# polivoks_ambika.net
KiCad netlist of a schematic drawn in EAGLE
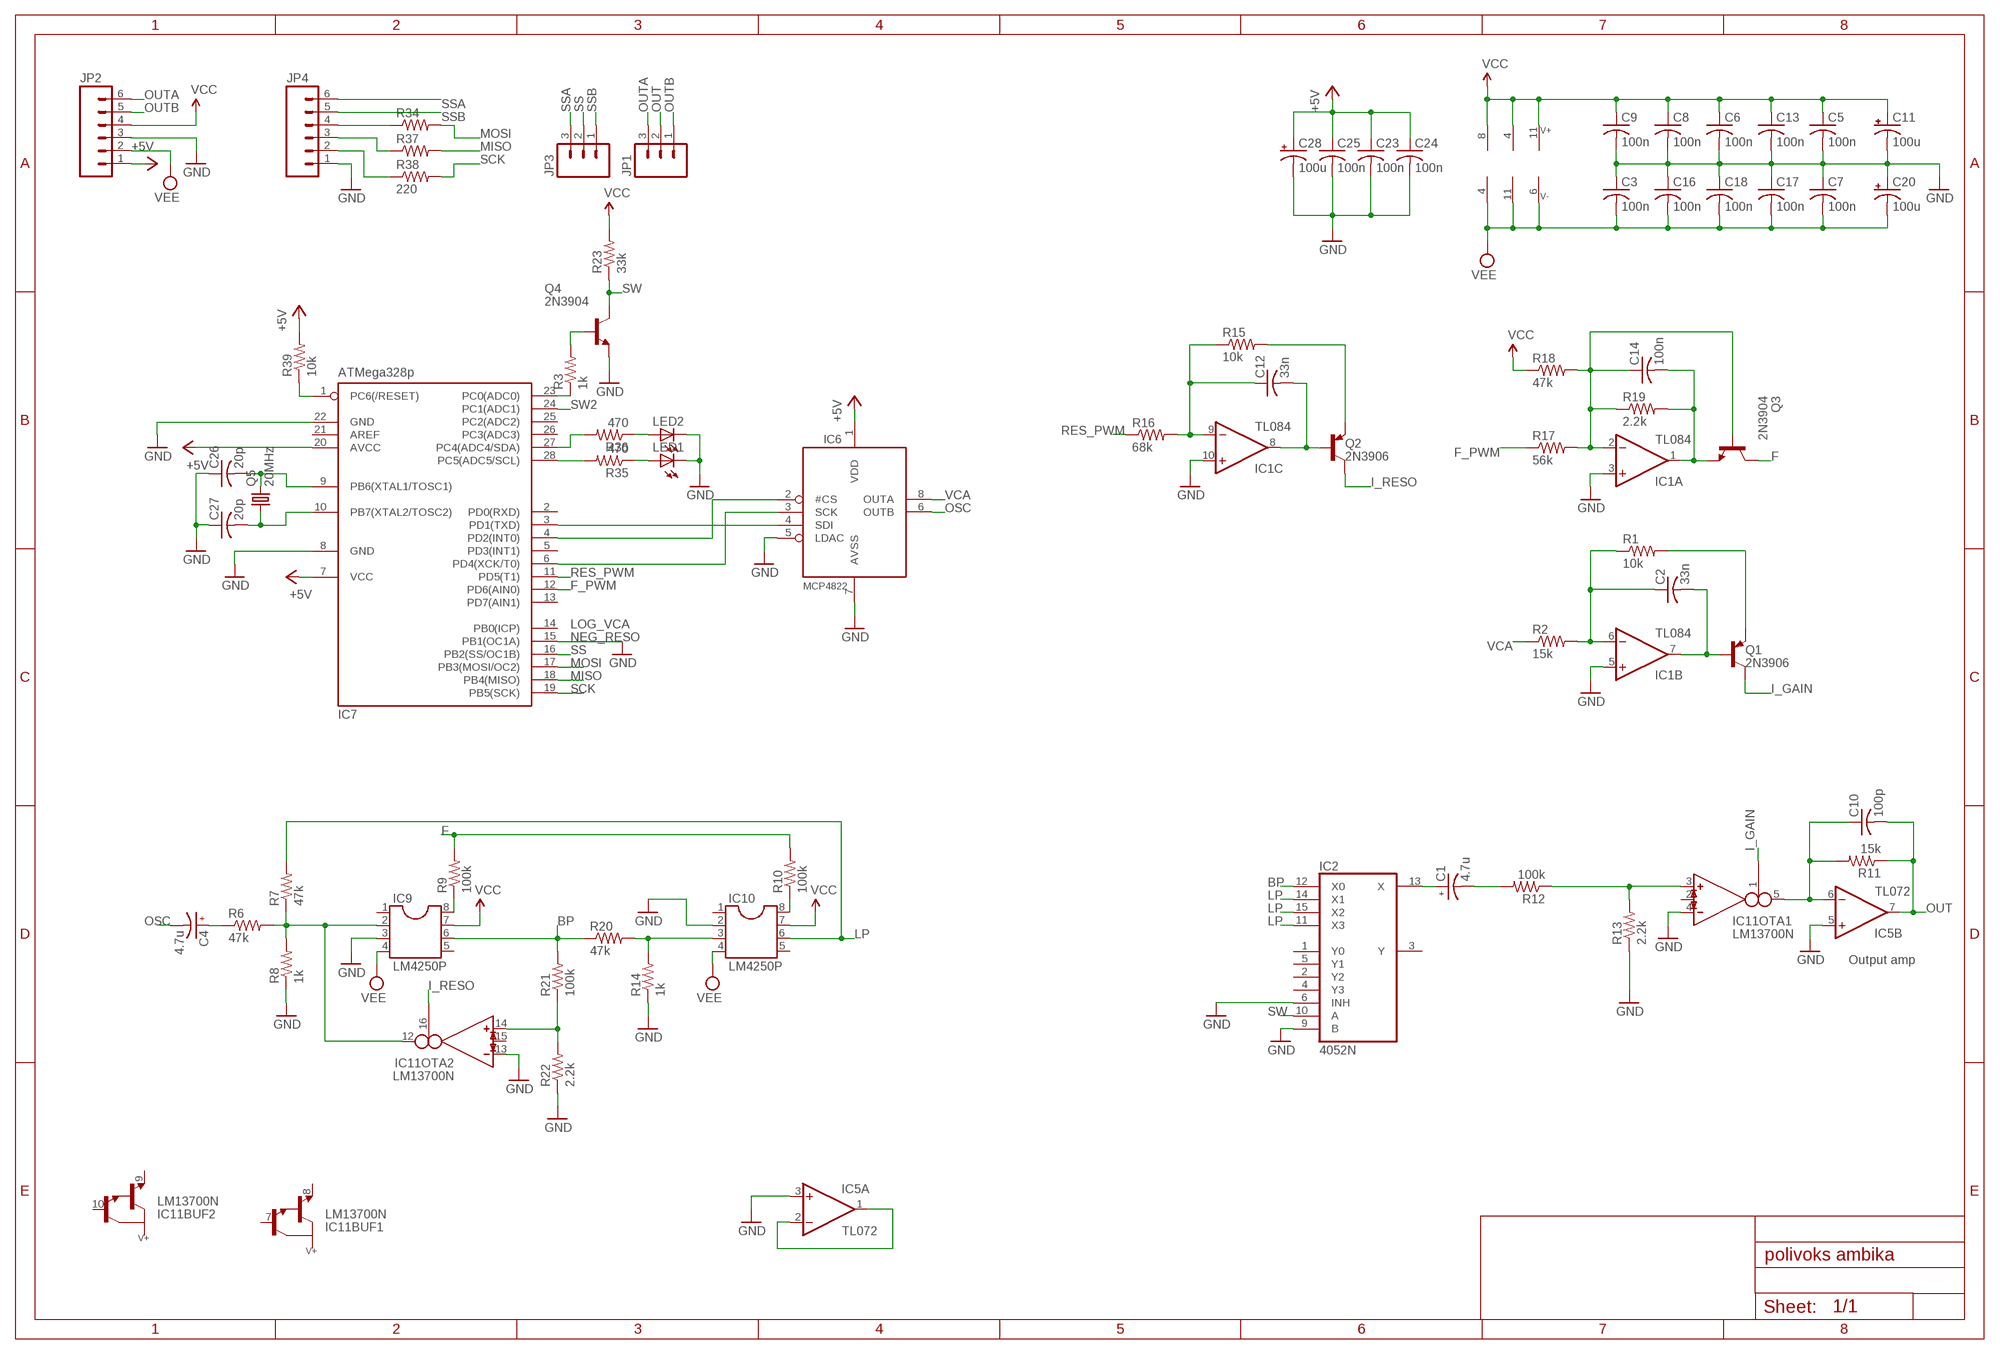
[diagram p0: schematic, sheet 1]

(export (version "E")
  (design (tool "Eeschema 10.0.6"))
  (components
    (comp (ref "C1")
      (value "4.7u")
      (footprint "eagle-import:E11-6.3")
      (libsource (lib "eagle-import") (part "CPOL-USE11-6.3"))
    )
    (comp (ref "C2")
      (value "33n")
      (footprint "eagle-import:C050-025X075")
      (libsource (lib "eagle-import") (part "C-US050-025X075"))
    )
    (comp (ref "C3")
      (value "100n")
      (footprint "eagle-import:C025-025X050")
      (libsource (lib "eagle-import") (part "C-US025-025X050"))
    )
    (comp (ref "C4")
      (value "4.7u")
      (footprint "eagle-import:E11-6.3")
      (libsource (lib "eagle-import") (part "CPOL-USE11-6.3"))
    )
    (comp (ref "C5")
      (value "100n")
      (footprint "eagle-import:C025-025X050")
      (libsource (lib "eagle-import") (part "C-US025-025X050"))
    )
    (comp (ref "C6")
      (value "100n")
      (footprint "eagle-import:C025-025X050")
      (libsource (lib "eagle-import") (part "C-US025-025X050"))
    )
    (comp (ref "C7")
      (value "100n")
      (footprint "eagle-import:C025-025X050")
      (libsource (lib "eagle-import") (part "C-US025-025X050"))
    )
    (comp (ref "C8")
      (value "100n")
      (footprint "eagle-import:C025-025X050")
      (libsource (lib "eagle-import") (part "C-US025-025X050"))
    )
    (comp (ref "C9")
      (value "100n")
      (footprint "eagle-import:C025-025X050")
      (libsource (lib "eagle-import") (part "C-US025-025X050"))
    )
    (comp (ref "C10")
      (value "100p")
      (footprint "eagle-import:C025-025X050")
      (libsource (lib "eagle-import") (part "C-US025-025X050"))
    )
    (comp (ref "C11")
      (value "100u")
      (footprint "eagle-import:E2,5-6")
      (libsource (lib "eagle-import") (part "CPOL-USE2.5-6"))
    )
    (comp (ref "C12")
      (value "33n")
      (footprint "eagle-import:C050-025X075")
      (libsource (lib "eagle-import") (part "C-US050-025X075"))
    )
    (comp (ref "C13")
      (value "100n")
      (footprint "eagle-import:C025-025X050")
      (libsource (lib "eagle-import") (part "C-US025-025X050"))
    )
    (comp (ref "C14")
      (value "100n")
      (footprint "eagle-import:C025-025X050")
      (libsource (lib "eagle-import") (part "C-US025-025X050"))
    )
    (comp (ref "C16")
      (value "100n")
      (footprint "eagle-import:C025-025X050")
      (libsource (lib "eagle-import") (part "C-US025-025X050"))
    )
    (comp (ref "C17")
      (value "100n")
      (footprint "eagle-import:C025-025X050")
      (libsource (lib "eagle-import") (part "C-US025-025X050"))
    )
    (comp (ref "C18")
      (value "100n")
      (footprint "eagle-import:C025-025X050")
      (libsource (lib "eagle-import") (part "C-US025-025X050"))
    )
    (comp (ref "C20")
      (value "100u")
      (footprint "eagle-import:E2,5-6")
      (libsource (lib "eagle-import") (part "CPOL-USE2.5-6"))
    )
    (comp (ref "C23")
      (value "100n")
      (footprint "eagle-import:C025-025X050")
      (libsource (lib "eagle-import") (part "C-US025-025X050"))
    )
    (comp (ref "C24")
      (value "100n")
      (footprint "eagle-import:C025-025X050")
      (libsource (lib "eagle-import") (part "C-US025-025X050"))
    )
    (comp (ref "C25")
      (value "100n")
      (footprint "eagle-import:C025-025X050")
      (libsource (lib "eagle-import") (part "C-US025-025X050"))
    )
    (comp (ref "C26")
      (value "20p")
      (footprint "eagle-import:C025-024X044")
      (libsource (lib "eagle-import") (part "C-US025-024X044"))
    )
    (comp (ref "C27")
      (value "20p")
      (footprint "eagle-import:C025-024X044")
      (libsource (lib "eagle-import") (part "C-US025-024X044"))
    )
    (comp (ref "C28")
      (value "100u")
      (footprint "eagle-import:E2,5-6")
      (libsource (lib "eagle-import") (part "CPOL-USE2.5-6"))
    )
    (comp (ref "IC1")
      (value "TL084")
      (footprint "eagle-import:DIL14")
      (libsource (lib "eagle-import") (part "TL084P"))
    )
    (comp (ref "IC2")
      (value "4052N")
      (footprint "eagle-import:DIL16")
      (libsource (lib "eagle-import") (part "4052N"))
    )
    (comp (ref "IC5")
      (value "TL072")
      (footprint "eagle-import:DIL08")
      (libsource (lib "eagle-import") (part "TL082P"))
    )
    (comp (ref "IC6")
      (value "MCP4822")
      (footprint "eagle-import:DIL08")
      (libsource (lib "eagle-import") (part "MCP4822"))
    )
    (comp (ref "IC7")
      (value "ATMega328p")
      (footprint "eagle-import:DIL28-3")
      (libsource (lib "eagle-import") (part "MEGA8-P"))
    )
    (comp (ref "IC9")
      (value "LM4250P")
      (footprint "eagle-import:DIL08")
      (libsource (lib "eagle-import") (part "DIL8"))
    )
    (comp (ref "IC10")
      (value "LM4250P")
      (footprint "eagle-import:DIL08")
      (libsource (lib "eagle-import") (part "DIL8"))
    )
    (comp (ref "IC11")
      (value "LM13700N")
      (footprint "eagle-import:DIL16")
      (libsource (lib "eagle-import") (part "LM13700N"))
    )
    (comp (ref "JP1")
      (value "M03PTH")
      (footprint "eagle-import:1X03")
      (libsource (lib "eagle-import") (part "M03PTH"))
    )
    (comp (ref "JP2")
      (value "M06SIP")
      (footprint "eagle-import:1X06")
      (libsource (lib "eagle-import") (part "M06SIP"))
    )
    (comp (ref "JP3")
      (value "M03PTH")
      (footprint "eagle-import:1X03")
      (libsource (lib "eagle-import") (part "M03PTH"))
    )
    (comp (ref "JP4")
      (value "M06SIP")
      (footprint "eagle-import:1X06")
      (libsource (lib "eagle-import") (part "M06SIP"))
    )
    (comp (ref "LED1")
      (value "LED3MM")
      (footprint "eagle-import:LED3MM")
      (libsource (lib "eagle-import") (part "LED3MM"))
    )
    (comp (ref "LED2")
      (value "LED3MM")
      (footprint "eagle-import:LED3MM")
      (libsource (lib "eagle-import") (part "LED3MM"))
    )
    (comp (ref "Q1")
      (value "2N3906")
      (footprint "eagle-import:TO92-")
      (libsource (lib "eagle-import") (part "2N3906-"))
    )
    (comp (ref "Q2")
      (value "2N3906")
      (footprint "eagle-import:TO92-")
      (libsource (lib "eagle-import") (part "2N3906-"))
    )
    (comp (ref "Q3")
      (value "2N3904")
      (footprint "eagle-import:TO92")
      (libsource (lib "eagle-import") (part "2N3904"))
    )
    (comp (ref "Q4")
      (value "2N3904")
      (footprint "eagle-import:TO92")
      (libsource (lib "eagle-import") (part "2N3904"))
    )
    (comp (ref "Q5")
      (value "20MHz")
      (footprint "eagle-import:HC49U-V")
      (libsource (lib "eagle-import") (part "CRYSTALHC49U-V"))
    )
    (comp (ref "R1")
      (value "10k")
      (footprint "eagle-import:0204_7")
      (libsource (lib "eagle-import") (part "R-US_0204/7"))
    )
    (comp (ref "R2")
      (value "15k")
      (footprint "eagle-import:0204_7")
      (libsource (lib "eagle-import") (part "R-US_0204/7"))
    )
    (comp (ref "R3")
      (value "1k")
      (footprint "eagle-import:0204_7")
      (libsource (lib "eagle-import") (part "R-US_0204/7"))
    )
    (comp (ref "R6")
      (value "47k")
      (footprint "eagle-import:0204_7")
      (libsource (lib "eagle-import") (part "R-US_0204/7"))
    )
    (comp (ref "R7")
      (value "47k")
      (footprint "eagle-import:0204_7")
      (libsource (lib "eagle-import") (part "R-US_0204/7"))
    )
    (comp (ref "R8")
      (value "1k")
      (footprint "eagle-import:0204_7")
      (libsource (lib "eagle-import") (part "R-US_0204/7"))
    )
    (comp (ref "R9")
      (value "100k")
      (footprint "eagle-import:0204_7")
      (libsource (lib "eagle-import") (part "R-US_0204/7"))
    )
    (comp (ref "R10")
      (value "100k")
      (footprint "eagle-import:0204_7")
      (libsource (lib "eagle-import") (part "R-US_0204/7"))
    )
    (comp (ref "R11")
      (value "15k")
      (footprint "eagle-import:0204_7")
      (libsource (lib "eagle-import") (part "R-US_0204/7"))
    )
    (comp (ref "R12")
      (value "100k")
      (footprint "eagle-import:0204_7")
      (libsource (lib "eagle-import") (part "R-US_0204/7"))
    )
    (comp (ref "R13")
      (value "2.2k")
      (footprint "eagle-import:0204_7")
      (libsource (lib "eagle-import") (part "R-US_0204/7"))
    )
    (comp (ref "R14")
      (value "1k")
      (footprint "eagle-import:0204_7")
      (libsource (lib "eagle-import") (part "R-US_0204/7"))
    )
    (comp (ref "R15")
      (value "10k")
      (footprint "eagle-import:0204_7")
      (libsource (lib "eagle-import") (part "R-US_0204/7"))
    )
    (comp (ref "R16")
      (value "68k")
      (footprint "eagle-import:0204_7")
      (libsource (lib "eagle-import") (part "R-US_0204/7"))
    )
    (comp (ref "R17")
      (value "56k")
      (footprint "eagle-import:0204_7")
      (libsource (lib "eagle-import") (part "R-US_0204/7"))
    )
    (comp (ref "R18")
      (value "47k")
      (footprint "eagle-import:0204_7")
      (libsource (lib "eagle-import") (part "R-US_0204/7"))
    )
    (comp (ref "R19")
      (value "2.2k")
      (footprint "eagle-import:0204_7")
      (libsource (lib "eagle-import") (part "R-US_0204/7"))
    )
    (comp (ref "R20")
      (value "47k")
      (footprint "eagle-import:0204_7")
      (libsource (lib "eagle-import") (part "R-US_0204/7"))
    )
    (comp (ref "R21")
      (value "100k")
      (footprint "eagle-import:0204_7")
      (libsource (lib "eagle-import") (part "R-US_0204/7"))
    )
    (comp (ref "R22")
      (value "2.2k")
      (footprint "eagle-import:0204_7")
      (libsource (lib "eagle-import") (part "R-US_0204/7"))
    )
    (comp (ref "R23")
      (value "33k")
      (footprint "eagle-import:0204_7")
      (libsource (lib "eagle-import") (part "R-US_0204/7"))
    )
    (comp (ref "R34")
      (value "220")
      (footprint "eagle-import:0204_7")
      (libsource (lib "eagle-import") (part "R-US_0204/7"))
    )
    (comp (ref "R35")
      (value "470")
      (footprint "eagle-import:0204_7")
      (libsource (lib "eagle-import") (part "R-US_0204/7"))
    )
    (comp (ref "R36")
      (value "470")
      (footprint "eagle-import:0204_7")
      (libsource (lib "eagle-import") (part "R-US_0204/7"))
    )
    (comp (ref "R37")
      (value "220")
      (footprint "eagle-import:0204_7")
      (libsource (lib "eagle-import") (part "R-US_0204/7"))
    )
    (comp (ref "R38")
      (value "220")
      (footprint "eagle-import:0204_7")
      (libsource (lib "eagle-import") (part "R-US_0204/7"))
    )
    (comp (ref "R39")
      (value "10k")
      (footprint "eagle-import:0204_7")
      (libsource (lib "eagle-import") (part "R-US_0204/7"))
    )
  )
  (nets
    (net (code "1") (name "+5V") (class "Default")
      (node (ref "C23") (pin "1") (pinfunction "1_1") (pintype "passive"))
      (node (ref "C24") (pin "1") (pinfunction "1_1") (pintype "passive"))
      (node (ref "C25") (pin "1") (pinfunction "1_1") (pintype "passive"))
      (node (ref "C28") (pin "+") (pinfunction "+_+") (pintype "passive"))
      (node (ref "IC6") (pin "1") (pinfunction "VDD_1") (pintype "power_in"))
      (node (ref "IC7") (pin "20") (pinfunction "AVCC_20") (pintype "power_in"))
      (node (ref "IC7") (pin "7") (pinfunction "VCC_7") (pintype "power_in"))
      (node (ref "JP2") (pin "1") (pinfunction "1_1") (pintype "passive"))
      (node (ref "R39") (pin "2") (pinfunction "2_2") (pintype "passive"))
    )
    (net (code "2") (name "/BP") (class "Default")
      (node (ref "IC2") (pin "12") (pinfunction "X0_12") (pintype "bidirectional"))
      (node (ref "IC9") (pin "6") (pinfunction "6_6") (pintype "passive"))
      (node (ref "R20") (pin "1") (pinfunction "1_1") (pintype "passive"))
      (node (ref "R21") (pin "2") (pinfunction "2_2") (pintype "passive"))
    )
    (net (code "3") (name "/F") (class "Default")
      (node (ref "Q3") (pin "1") (pinfunction "C_1") (pintype "passive"))
      (node (ref "R10") (pin "2") (pinfunction "2_2") (pintype "passive"))
      (node (ref "R9") (pin "2") (pinfunction "2_2") (pintype "passive"))
    )
    (net (code "4") (name "/F_PWM") (class "Default")
      (node (ref "IC7") (pin "12") (pinfunction "PD6(AIN0)_12") (pintype "bidirectional"))
      (node (ref "R17") (pin "1") (pinfunction "1_1") (pintype "passive"))
    )
    (net (code "5") (name "/I_GAIN") (class "Default")
      (node (ref "IC11") (pin "1") (pinfunction "I_BIAS_1") (pintype "input"))
      (node (ref "Q1") (pin "1") (pinfunction "C_1") (pintype "passive"))
    )
    (net (code "6") (name "/I_RESO") (class "Default")
      (node (ref "IC11") (pin "16") (pinfunction "I_BIAS_16") (pintype "input"))
      (node (ref "Q2") (pin "1") (pinfunction "C_1") (pintype "passive"))
    )
    (net (code "7") (name "/LP") (class "Default")
      (node (ref "IC10") (pin "6") (pinfunction "6_6") (pintype "passive"))
      (node (ref "IC2") (pin "11") (pinfunction "X3_11") (pintype "bidirectional"))
      (node (ref "IC2") (pin "14") (pinfunction "X1_14") (pintype "bidirectional"))
      (node (ref "IC2") (pin "15") (pinfunction "X2_15") (pintype "bidirectional"))
      (node (ref "R7") (pin "2") (pinfunction "2_2") (pintype "passive"))
    )
    (net (code "8") (name "/MISO") (class "Default")
      (node (ref "IC7") (pin "18") (pinfunction "PB4(MISO)_18") (pintype "bidirectional"))
      (node (ref "R37") (pin "2") (pinfunction "2_2") (pintype "passive"))
    )
    (net (code "9") (name "/MOSI") (class "Default")
      (node (ref "IC7") (pin "17") (pinfunction "PB3(MOSI/OC2)_17") (pintype "bidirectional"))
      (node (ref "R34") (pin "2") (pinfunction "2_2") (pintype "passive"))
    )
    (net (code "10") (name "/OSC") (class "Default")
      (node (ref "C4") (pin "-") (pinfunction "2_-") (pintype "passive"))
      (node (ref "IC6") (pin "6") (pinfunction "OUTB_6") (pintype "output"))
    )
    (net (code "11") (name "/OUT") (class "Default")
      (node (ref "C10") (pin "2") (pinfunction "2_2") (pintype "passive"))
      (node (ref "IC5") (pin "7") (pinfunction "OUT_7") (pintype "output"))
      (node (ref "JP1") (pin "2") (pinfunction "2_2") (pintype "passive"))
      (node (ref "R11") (pin "1") (pinfunction "1_1") (pintype "passive"))
    )
    (net (code "12") (name "/OUTA") (class "Default")
      (node (ref "JP1") (pin "3") (pinfunction "3_3") (pintype "passive"))
      (node (ref "JP2") (pin "6") (pinfunction "6_6") (pintype "passive"))
    )
    (net (code "13") (name "/OUTB") (class "Default")
      (node (ref "JP1") (pin "1") (pinfunction "1_1") (pintype "passive"))
      (node (ref "JP2") (pin "5") (pinfunction "5_5") (pintype "passive"))
    )
    (net (code "14") (name "/RES_PWM") (class "Default")
      (node (ref "IC7") (pin "11") (pinfunction "PD5(T1)_11") (pintype "bidirectional"))
      (node (ref "R16") (pin "1") (pinfunction "1_1") (pintype "passive"))
    )
    (net (code "15") (name "/SCK") (class "Default")
      (node (ref "IC7") (pin "19") (pinfunction "PB5(SCK)_19") (pintype "bidirectional"))
      (node (ref "R38") (pin "2") (pinfunction "2_2") (pintype "passive"))
    )
    (net (code "16") (name "/SS") (class "Default")
      (node (ref "IC7") (pin "16") (pinfunction "PB2(SS/OC1B)_16") (pintype "bidirectional"))
      (node (ref "JP3") (pin "2") (pinfunction "2_2") (pintype "passive"))
    )
    (net (code "17") (name "/SSA") (class "Default")
      (node (ref "JP3") (pin "3") (pinfunction "3_3") (pintype "passive"))
      (node (ref "JP4") (pin "6") (pinfunction "6_6") (pintype "passive"))
    )
    (net (code "18") (name "/SSB") (class "Default")
      (node (ref "JP3") (pin "1") (pinfunction "1_1") (pintype "passive"))
      (node (ref "JP4") (pin "5") (pinfunction "5_5") (pintype "passive"))
    )
    (net (code "19") (name "/SW") (class "Default")
      (node (ref "IC2") (pin "10") (pinfunction "A_10") (pintype "input"))
      (node (ref "Q4") (pin "1") (pinfunction "C_1") (pintype "passive"))
      (node (ref "R23") (pin "1") (pinfunction "1_1") (pintype "passive"))
    )
    (net (code "20") (name "/SW2") (class "Default")
      (node (ref "IC7") (pin "24") (pinfunction "PC1(ADC1)_24") (pintype "bidirectional"))
    )
    (net (code "21") (name "/VCA") (class "Default")
      (node (ref "IC6") (pin "8") (pinfunction "OUTA_8") (pintype "output"))
      (node (ref "R2") (pin "1") (pinfunction "1_1") (pintype "passive"))
    )
    (net (code "22") (name "GND") (class "Default")
      (node (ref "C11") (pin "-") (pinfunction "-_-") (pintype "passive"))
      (node (ref "C13") (pin "2") (pinfunction "2_2") (pintype "passive"))
      (node (ref "C16") (pin "1") (pinfunction "1_1") (pintype "passive"))
      (node (ref "C17") (pin "1") (pinfunction "1_1") (pintype "passive"))
      (node (ref "C18") (pin "1") (pinfunction "1_1") (pintype "passive"))
      (node (ref "C20") (pin "+") (pinfunction "+_+") (pintype "passive"))
      (node (ref "C23") (pin "2") (pinfunction "2_2") (pintype "passive"))
      (node (ref "C24") (pin "2") (pinfunction "2_2") (pintype "passive"))
      (node (ref "C25") (pin "2") (pinfunction "2_2") (pintype "passive"))
      (node (ref "C26") (pin "1") (pinfunction "1_1") (pintype "passive"))
      (node (ref "C27") (pin "1") (pinfunction "1_1") (pintype "passive"))
      (node (ref "C28") (pin "-") (pinfunction "-_-") (pintype "passive"))
      (node (ref "C3") (pin "1") (pinfunction "1_1") (pintype "passive"))
      (node (ref "C5") (pin "2") (pinfunction "2_2") (pintype "passive"))
      (node (ref "C6") (pin "2") (pinfunction "2_2") (pintype "passive"))
      (node (ref "C7") (pin "1") (pinfunction "1_1") (pintype "passive"))
      (node (ref "C8") (pin "2") (pinfunction "2_2") (pintype "passive"))
      (node (ref "C9") (pin "2") (pinfunction "2_2") (pintype "passive"))
      (node (ref "IC1") (pin "10") (pinfunction "+IN_10") (pintype "input"))
      (node (ref "IC1") (pin "3") (pinfunction "+IN_3") (pintype "input"))
      (node (ref "IC1") (pin "5") (pinfunction "+IN_5") (pintype "input"))
      (node (ref "IC10") (pin "2") (pinfunction "2_2") (pintype "passive"))
      (node (ref "IC11") (pin "13") (pinfunction "IN_N_13") (pintype "input"))
      (node (ref "IC11") (pin "4") (pinfunction "IN_N_4") (pintype "input"))
      (node (ref "IC2") (pin "6") (pinfunction "INH_6") (pintype "input"))
      (node (ref "IC2") (pin "9") (pinfunction "B_9") (pintype "input"))
      (node (ref "IC5") (pin "3") (pinfunction "+IN_3") (pintype "input"))
      (node (ref "IC5") (pin "5") (pinfunction "+IN_5") (pintype "input"))
      (node (ref "IC6") (pin "5") (pinfunction "LDAC_5") (pintype "input"))
      (node (ref "IC6") (pin "7") (pinfunction "AVSS_7") (pintype "power_in"))
      (node (ref "IC7") (pin "15") (pinfunction "PB1(OC1A)_15") (pintype "bidirectional"))
      (node (ref "IC7") (pin "22") (pinfunction "GND_22") (pintype "power_in"))
      (node (ref "IC7") (pin "8") (pinfunction "GND_8") (pintype "power_in"))
      (node (ref "IC9") (pin "3") (pinfunction "3_3") (pintype "passive"))
      (node (ref "JP2") (pin "3") (pinfunction "3_3") (pintype "passive"))
      (node (ref "JP4") (pin "1") (pinfunction "1_1") (pintype "passive"))
      (node (ref "LED1") (pin "K") (pinfunction "C_K") (pintype "passive"))
      (node (ref "LED2") (pin "K") (pinfunction "C_K") (pintype "passive"))
      (node (ref "Q4") (pin "3") (pinfunction "E_3") (pintype "passive"))
      (node (ref "R13") (pin "1") (pinfunction "1_1") (pintype "passive"))
      (node (ref "R14") (pin "1") (pinfunction "1_1") (pintype "passive"))
      (node (ref "R22") (pin "1") (pinfunction "1_1") (pintype "passive"))
      (node (ref "R8") (pin "1") (pinfunction "1_1") (pintype "passive"))
    )
    (net (code "23") (name "Net-(C1-1)") (class "Default")
      (node (ref "C1") (pin "+") (pinfunction "1_+") (pintype "passive"))
      (node (ref "IC2") (pin "13") (pinfunction "X_13") (pintype "bidirectional"))
    )
    (net (code "24") (name "Net-(C1-2)") (class "Default")
      (node (ref "C1") (pin "-") (pinfunction "2_-") (pintype "passive"))
      (node (ref "R12") (pin "2") (pinfunction "2_2") (pintype "passive"))
    )
    (net (code "25") (name "Net-(C4-1)") (class "Default")
      (node (ref "C4") (pin "+") (pinfunction "1_+") (pintype "passive"))
      (node (ref "R6") (pin "1") (pinfunction "1_1") (pintype "passive"))
    )
    (net (code "26") (name "Net-(IC1A--IN)") (class "Default")
      (node (ref "C14") (pin "1") (pinfunction "1_1") (pintype "passive"))
      (node (ref "IC1") (pin "2") (pinfunction "-IN_2") (pintype "input"))
      (node (ref "Q3") (pin "2") (pinfunction "B_2") (pintype "passive"))
      (node (ref "R17") (pin "2") (pinfunction "2_2") (pintype "passive"))
      (node (ref "R18") (pin "2") (pinfunction "2_2") (pintype "passive"))
      (node (ref "R19") (pin "1") (pinfunction "1_1") (pintype "passive"))
    )
    (net (code "27") (name "Net-(IC1A-OUT)") (class "Default")
      (node (ref "C14") (pin "2") (pinfunction "2_2") (pintype "passive"))
      (node (ref "IC1") (pin "1") (pinfunction "OUT_1") (pintype "output"))
      (node (ref "Q3") (pin "3") (pinfunction "E_3") (pintype "passive"))
      (node (ref "R19") (pin "2") (pinfunction "2_2") (pintype "passive"))
    )
    (net (code "28") (name "Net-(IC1B--IN)") (class "Default")
      (node (ref "C2") (pin "1") (pinfunction "1_1") (pintype "passive"))
      (node (ref "IC1") (pin "6") (pinfunction "-IN_6") (pintype "input"))
      (node (ref "R1") (pin "1") (pinfunction "1_1") (pintype "passive"))
      (node (ref "R2") (pin "2") (pinfunction "2_2") (pintype "passive"))
    )
    (net (code "29") (name "Net-(IC1B-OUT)") (class "Default")
      (node (ref "C2") (pin "2") (pinfunction "2_2") (pintype "passive"))
      (node (ref "IC1") (pin "7") (pinfunction "OUT_7") (pintype "output"))
      (node (ref "Q1") (pin "2") (pinfunction "B_2") (pintype "passive"))
    )
    (net (code "30") (name "Net-(IC1C--IN)") (class "Default")
      (node (ref "C12") (pin "1") (pinfunction "1_1") (pintype "passive"))
      (node (ref "IC1") (pin "9") (pinfunction "-IN_9") (pintype "input"))
      (node (ref "R15") (pin "1") (pinfunction "1_1") (pintype "passive"))
      (node (ref "R16") (pin "2") (pinfunction "2_2") (pintype "passive"))
    )
    (net (code "31") (name "Net-(IC1C-OUT)") (class "Default")
      (node (ref "C12") (pin "2") (pinfunction "2_2") (pintype "passive"))
      (node (ref "IC1") (pin "8") (pinfunction "OUT_8") (pintype "output"))
      (node (ref "Q2") (pin "2") (pinfunction "B_2") (pintype "passive"))
    )
    (net (code "32") (name "Net-(IC5A--IN)") (class "Default")
      (node (ref "IC5") (pin "1") (pinfunction "OUT_1") (pintype "output"))
      (node (ref "IC5") (pin "2") (pinfunction "-IN_2") (pintype "input"))
    )
    (net (code "33") (name "Net-(IC6-#CS)") (class "Default")
      (node (ref "IC6") (pin "2") (pinfunction "#CS_2") (pintype "input"))
      (node (ref "IC7") (pin "4") (pinfunction "PD2(INT0)_4") (pintype "bidirectional"))
    )
    (net (code "34") (name "Net-(IC6-SCK)") (class "Default")
      (node (ref "IC6") (pin "3") (pinfunction "SCK_3") (pintype "input"))
      (node (ref "IC7") (pin "6") (pinfunction "PD4(XCK/T0)_6") (pintype "bidirectional"))
    )
    (net (code "35") (name "Net-(IC6-SDI)") (class "Default")
      (node (ref "IC6") (pin "4") (pinfunction "SDI_4") (pintype "input"))
      (node (ref "IC7") (pin "3") (pinfunction "PD1(TXD)_3") (pintype "bidirectional"))
    )
    (net (code "36") (name "Net-(IC7-PB6(XTAL1{slash}TOSC1))") (class "Default")
      (node (ref "C26") (pin "2") (pinfunction "2_2") (pintype "passive"))
      (node (ref "IC7") (pin "9") (pinfunction "PB6(XTAL1/TOSC1)_9") (pintype "bidirectional"))
      (node (ref "Q5") (pin "2") (pinfunction "2_2") (pintype "passive"))
    )
    (net (code "37") (name "Net-(IC7-PB7(XTAL2{slash}TOSC2))") (class "Default")
      (node (ref "C27") (pin "2") (pinfunction "2_2") (pintype "passive"))
      (node (ref "IC7") (pin "10") (pinfunction "PB7(XTAL2/TOSC2)_10") (pintype "bidirectional"))
      (node (ref "Q5") (pin "1") (pinfunction "1_1") (pintype "passive"))
    )
    (net (code "38") (name "Net-(IC7-PC0(ADC0))") (class "Default")
      (node (ref "IC7") (pin "23") (pinfunction "PC0(ADC0)_23") (pintype "bidirectional"))
      (node (ref "R3") (pin "1") (pinfunction "1_1") (pintype "passive"))
    )
    (net (code "39") (name "Net-(IC7-PC4(ADC4{slash}SDA))") (class "Default")
      (node (ref "IC7") (pin "27") (pinfunction "PC4(ADC4/SDA)_27") (pintype "bidirectional"))
      (node (ref "R36") (pin "2") (pinfunction "2_2") (pintype "passive"))
    )
    (net (code "40") (name "Net-(IC7-PC5(ADC5{slash}SCL))") (class "Default")
      (node (ref "IC7") (pin "28") (pinfunction "PC5(ADC5/SCL)_28") (pintype "bidirectional"))
      (node (ref "R35") (pin "2") (pinfunction "2_2") (pintype "passive"))
    )
    (net (code "41") (name "Net-(IC7-PC6({slash}RESET))") (class "Default")
      (node (ref "IC7") (pin "1") (pinfunction "PC6(/RESET)_1") (pintype "bidirectional"))
      (node (ref "R39") (pin "1") (pinfunction "1_1") (pintype "passive"))
    )
    (net (code "42") (name "Net-(IC9-Pad8)") (class "Default")
      (node (ref "IC9") (pin "8") (pinfunction "8_8") (pintype "passive"))
      (node (ref "R9") (pin "1") (pinfunction "1_1") (pintype "passive"))
    )
    (net (code "43") (name "Net-(IC10-Pad3)") (class "Default")
      (node (ref "IC10") (pin "3") (pinfunction "3_3") (pintype "passive"))
      (node (ref "R14") (pin "2") (pinfunction "2_2") (pintype "passive"))
      (node (ref "R20") (pin "2") (pinfunction "2_2") (pintype "passive"))
    )
    (net (code "44") (name "Net-(IC10-Pad8)") (class "Default")
      (node (ref "IC10") (pin "8") (pinfunction "8_8") (pintype "passive"))
      (node (ref "R10") (pin "1") (pinfunction "1_1") (pintype "passive"))
    )
    (net (code "45") (name "Net-(IC11C-IN_P)") (class "Default")
      (node (ref "IC11") (pin "3") (pinfunction "IN_P_3") (pintype "input"))
      (node (ref "R12") (pin "1") (pinfunction "1_1") (pintype "passive"))
      (node (ref "R13") (pin "2") (pinfunction "2_2") (pintype "passive"))
    )
    (net (code "46") (name "Net-(IC11C-OUT)") (class "Default")
      (node (ref "C10") (pin "1") (pinfunction "1_1") (pintype "passive"))
      (node (ref "IC11") (pin "5") (pinfunction "OUT_5") (pintype "output"))
      (node (ref "IC5") (pin "6") (pinfunction "-IN_6") (pintype "input"))
      (node (ref "R11") (pin "2") (pinfunction "2_2") (pintype "passive"))
    )
    (net (code "47") (name "Net-(IC11D-IN_P)") (class "Default")
      (node (ref "IC11") (pin "14") (pinfunction "IN_P_14") (pintype "input"))
      (node (ref "R21") (pin "1") (pinfunction "1_1") (pintype "passive"))
      (node (ref "R22") (pin "2") (pinfunction "2_2") (pintype "passive"))
    )
    (net (code "48") (name "Net-(IC11D-OUT)") (class "Default")
      (node (ref "IC11") (pin "12") (pinfunction "OUT_12") (pintype "output"))
      (node (ref "IC9") (pin "2") (pinfunction "2_2") (pintype "passive"))
      (node (ref "R6") (pin "2") (pinfunction "2_2") (pintype "passive"))
      (node (ref "R7") (pin "1") (pinfunction "1_1") (pintype "passive"))
      (node (ref "R8") (pin "2") (pinfunction "2_2") (pintype "passive"))
    )
    (net (code "49") (name "Net-(JP4-Pad2)") (class "Default")
      (node (ref "JP4") (pin "2") (pinfunction "2_2") (pintype "passive"))
      (node (ref "R38") (pin "1") (pinfunction "1_1") (pintype "passive"))
    )
    (net (code "50") (name "Net-(JP4-Pad3)") (class "Default")
      (node (ref "JP4") (pin "3") (pinfunction "3_3") (pintype "passive"))
      (node (ref "R37") (pin "1") (pinfunction "1_1") (pintype "passive"))
    )
    (net (code "51") (name "Net-(JP4-Pad4)") (class "Default")
      (node (ref "JP4") (pin "4") (pinfunction "4_4") (pintype "passive"))
      (node (ref "R34") (pin "1") (pinfunction "1_1") (pintype "passive"))
    )
    (net (code "52") (name "Net-(LED1-PadA)") (class "Default")
      (node (ref "LED1") (pin "A") (pinfunction "A_A") (pintype "passive"))
      (node (ref "R35") (pin "1") (pinfunction "1_1") (pintype "passive"))
    )
    (net (code "53") (name "Net-(LED2-PadA)") (class "Default")
      (node (ref "LED2") (pin "A") (pinfunction "A_A") (pintype "passive"))
      (node (ref "R36") (pin "1") (pinfunction "1_1") (pintype "passive"))
    )
    (net (code "54") (name "Net-(Q1-E)") (class "Default")
      (node (ref "Q1") (pin "3") (pinfunction "E_3") (pintype "passive"))
      (node (ref "R1") (pin "2") (pinfunction "2_2") (pintype "passive"))
    )
    (net (code "55") (name "Net-(Q2-E)") (class "Default")
      (node (ref "Q2") (pin "3") (pinfunction "E_3") (pintype "passive"))
      (node (ref "R15") (pin "2") (pinfunction "2_2") (pintype "passive"))
    )
    (net (code "56") (name "Net-(Q4-B)") (class "Default")
      (node (ref "Q4") (pin "2") (pinfunction "B_2") (pintype "passive"))
      (node (ref "R3") (pin "2") (pinfunction "2_2") (pintype "passive"))
    )
    (net (code "57") (name "VCC") (class "Default")
      (node (ref "C11") (pin "+") (pinfunction "+_+") (pintype "passive"))
      (node (ref "C13") (pin "1") (pinfunction "1_1") (pintype "passive"))
      (node (ref "C5") (pin "1") (pinfunction "1_1") (pintype "passive"))
      (node (ref "C6") (pin "1") (pinfunction "1_1") (pintype "passive"))
      (node (ref "C8") (pin "1") (pinfunction "1_1") (pintype "passive"))
      (node (ref "C9") (pin "1") (pinfunction "1_1") (pintype "passive"))
      (node (ref "IC1") (pin "4") (pinfunction "V+_4") (pintype "power_in"))
      (node (ref "IC10") (pin "7") (pinfunction "7_7") (pintype "passive"))
      (node (ref "IC11") (pin "11") (pinfunction "V+_11") (pintype "power_in"))
      (node (ref "IC5") (pin "8") (pinfunction "V+_8") (pintype "power_in"))
      (node (ref "IC9") (pin "7") (pinfunction "7_7") (pintype "passive"))
      (node (ref "JP2") (pin "4") (pinfunction "4_4") (pintype "passive"))
      (node (ref "R18") (pin "1") (pinfunction "1_1") (pintype "passive"))
      (node (ref "R23") (pin "2") (pinfunction "2_2") (pintype "passive"))
    )
    (net (code "58") (name "VEE") (class "Default")
      (node (ref "C16") (pin "2") (pinfunction "2_2") (pintype "passive"))
      (node (ref "C17") (pin "2") (pinfunction "2_2") (pintype "passive"))
      (node (ref "C18") (pin "2") (pinfunction "2_2") (pintype "passive"))
      (node (ref "C20") (pin "-") (pinfunction "-_-") (pintype "passive"))
      (node (ref "C3") (pin "2") (pinfunction "2_2") (pintype "passive"))
      (node (ref "C7") (pin "2") (pinfunction "2_2") (pintype "passive"))
      (node (ref "IC1") (pin "11") (pinfunction "V-_11") (pintype "power_in"))
      (node (ref "IC10") (pin "4") (pinfunction "4_4") (pintype "passive"))
      (node (ref "IC11") (pin "6") (pinfunction "V-_6") (pintype "power_in"))
      (node (ref "IC5") (pin "4") (pinfunction "V-_4") (pintype "power_in"))
      (node (ref "IC9") (pin "4") (pinfunction "4_4") (pintype "passive"))
      (node (ref "JP2") (pin "2") (pinfunction "2_2") (pintype "passive"))
    )
    (net (code "59") (name "unconnected-(IC2A-Y-Pad3)") (class "Default")
      (node (ref "IC2") (pin "3") (pinfunction "Y_3") (pintype "bidirectional"))
    )
    (net (code "60") (name "unconnected-(IC2A-Y0-Pad1)") (class "Default")
      (node (ref "IC2") (pin "1") (pinfunction "Y0_1") (pintype "bidirectional"))
    )
    (net (code "61") (name "unconnected-(IC2A-Y1-Pad5)") (class "Default")
      (node (ref "IC2") (pin "5") (pinfunction "Y1_5") (pintype "bidirectional"))
    )
    (net (code "62") (name "unconnected-(IC2A-Y2-Pad2)") (class "Default")
      (node (ref "IC2") (pin "2") (pinfunction "Y2_2") (pintype "bidirectional"))
    )
    (net (code "63") (name "unconnected-(IC2A-Y3-Pad4)") (class "Default")
      (node (ref "IC2") (pin "4") (pinfunction "Y3_4") (pintype "bidirectional"))
    )
    (net (code "64") (name "unconnected-(IC7-AREF-Pad21)") (class "Default")
      (node (ref "IC7") (pin "21") (pinfunction "AREF_21") (pintype "passive"))
    )
    (net (code "65") (name "unconnected-(IC7-PB0(ICP)-Pad14)") (class "Default")
      (node (ref "IC7") (pin "14") (pinfunction "PB0(ICP)_14") (pintype "bidirectional"))
    )
    (net (code "66") (name "unconnected-(IC7-PC2(ADC2)-Pad25)") (class "Default")
      (node (ref "IC7") (pin "25") (pinfunction "PC2(ADC2)_25") (pintype "bidirectional"))
    )
    (net (code "67") (name "unconnected-(IC7-PC3(ADC3)-Pad26)") (class "Default")
      (node (ref "IC7") (pin "26") (pinfunction "PC3(ADC3)_26") (pintype "bidirectional"))
    )
    (net (code "68") (name "unconnected-(IC7-PD0(RXD)-Pad2)") (class "Default")
      (node (ref "IC7") (pin "2") (pinfunction "PD0(RXD)_2") (pintype "bidirectional"))
    )
    (net (code "69") (name "unconnected-(IC7-PD3(INT1)-Pad5)") (class "Default")
      (node (ref "IC7") (pin "5") (pinfunction "PD3(INT1)_5") (pintype "bidirectional"))
    )
    (net (code "70") (name "unconnected-(IC7-PD7(AIN1)-Pad13)") (class "Default")
      (node (ref "IC7") (pin "13") (pinfunction "PD7(AIN1)_13") (pintype "bidirectional"))
    )
    (net (code "71") (name "unconnected-(IC9-Pad1)") (class "Default")
      (node (ref "IC9") (pin "1") (pinfunction "1_1") (pintype "passive"))
    )
    (net (code "72") (name "unconnected-(IC9-Pad5)") (class "Default")
      (node (ref "IC9") (pin "5") (pinfunction "5_5") (pintype "passive"))
    )
    (net (code "73") (name "unconnected-(IC10-Pad1)") (class "Default")
      (node (ref "IC10") (pin "1") (pinfunction "1_1") (pintype "passive"))
    )
    (net (code "74") (name "unconnected-(IC10-Pad5)") (class "Default")
      (node (ref "IC10") (pin "5") (pinfunction "5_5") (pintype "passive"))
    )
    (net (code "75") (name "unconnected-(IC11A-B-Pad7)") (class "Default")
      (node (ref "IC11") (pin "7") (pinfunction "B_7") (pintype "passive"))
    )
    (net (code "76") (name "unconnected-(IC11A-E-Pad8)") (class "Default")
      (node (ref "IC11") (pin "8") (pinfunction "E_8") (pintype "passive"))
    )
    (net (code "77") (name "unconnected-(IC11B-B-Pad10)") (class "Default")
      (node (ref "IC11") (pin "10") (pinfunction "B_10") (pintype "passive"))
    )
    (net (code "78") (name "unconnected-(IC11B-E-Pad9)") (class "Default")
      (node (ref "IC11") (pin "9") (pinfunction "E_9") (pintype "passive"))
    )
    (net (code "79") (name "unconnected-(IC11C-I_DIODE-Pad2)") (class "Default")
      (node (ref "IC11") (pin "2") (pinfunction "I_DIODE_2") (pintype "input"))
    )
    (net (code "80") (name "unconnected-(IC11D-I_DIODE-Pad15)") (class "Default")
      (node (ref "IC11") (pin "15") (pinfunction "I_DIODE_15") (pintype "input"))
    )
  )
)
